# Sheet1.net
KiCad netlist of a schematic drawn in Altium Designer
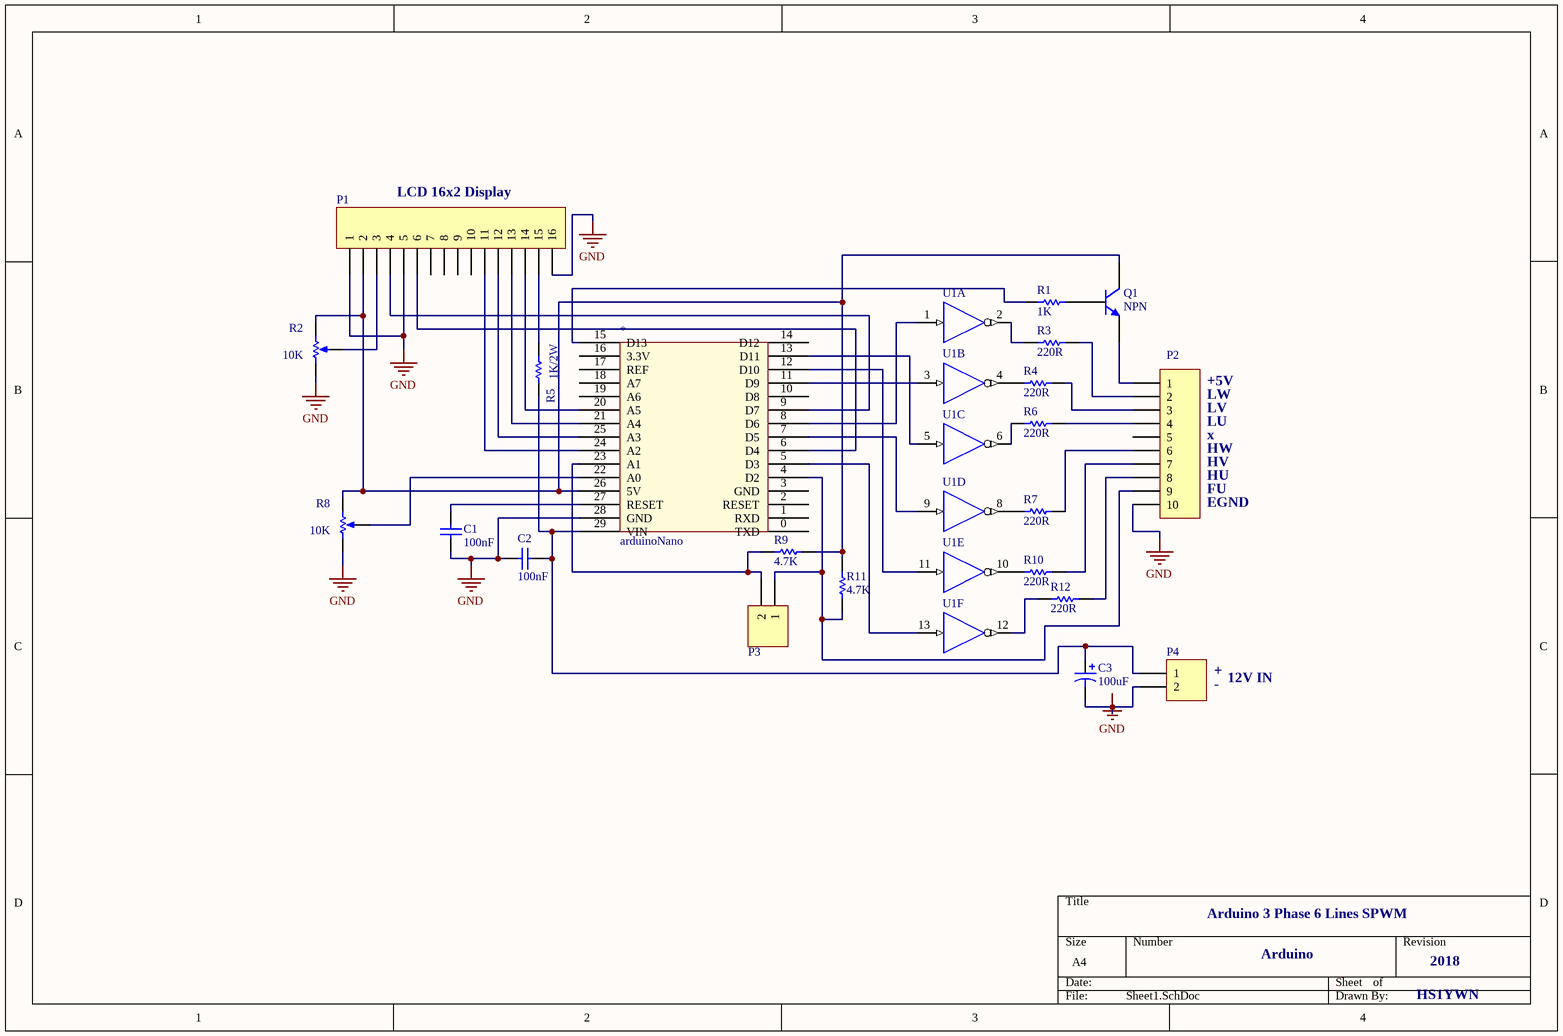
[diagram p0: Sheet1.SchDoc]

(export (version "E")
  (design (tool "Eeschema 10.0.6"))
  (components
    (comp (ref "*")
      (value "arduinoNano")
      (footprint "Arduino nano")
      (libsource (lib "nanoArduino") (part "arduinoNano"))
    )
    (comp (ref "C1")
      (value "100nF")
      (footprint "CE_200")
      (description "Capacitor")
      (fields (field (name "PUBLISHER") "Altium Limited"))
      (libsource (lib "PCB_PS21244_Project") (part "Cap"))
    )
    (comp (ref "C2")
      (value "100nF")
      (footprint "CE_200")
      (description "Capacitor")
      (fields (field (name "PUBLISHER") "Altium Limited"))
      (libsource (lib "PCB_PS21244_Project") (part "Cap"))
    )
    (comp (ref "C3")
      (value "100uF")
      (footprint "CAN_150")
      (description "Capacitor (Radial)")
      (fields (field (name "PUBLISHER") "Altium Limited"))
      (libsource (lib "PCB_PS21244_Project") (part "Cap Pol1"))
    )
    (comp (ref "P1")
      (value "Header 16")
      (footprint "HDR1X16")
      (description "Header, 16-Pin")
      (fields (field (name "PUBLISHER") "Altium Limited"))
      (libsource (lib "Miscellaneous Connectors") (part "Header 16"))
    )
    (comp (ref "P2")
      (value "Header 10")
      (footprint "HDR1X10")
      (description "Header, 10-Pin")
      (fields (field (name "PUBLISHER") "Altium Limited"))
      (libsource (lib "Miscellaneous Connectors") (part "Header 10"))
    )
    (comp (ref "P3")
      (value "Header 2")
      (footprint "HDR1X2")
      (description "Header, 2-Pin")
      (fields (field (name "PUBLISHER") "Altium Limited"))
      (libsource (lib "Miscellaneous Connectors") (part "Header 2"))
    )
    (comp (ref "P4")
      (value "Header 2")
      (footprint "HDR1X2")
      (description "Header, 2-Pin")
      (fields (field (name "PUBLISHER") "Altium Limited"))
      (libsource (lib "") (part "Header 2_1"))
    )
    (comp (ref "Q1")
      (value "NPN")
      (footprint "TO-226-AA")
      (description "NPN Bipolar Transistor")
      (fields (field (name "PUBLISHER") "Altium Limited"))
      (libsource (lib "Miscellaneous Devices") (part "NPN"))
    )
    (comp (ref "R1")
      (value "1K")
      (footprint "AXIAL-0.3")
      (description "Resistor")
      (fields (field (name "PUBLISHER") "Altium Limited"))
      (libsource (lib "Miscellaneous Devices") (part "Res1"))
    )
    (comp (ref "R2")
      (value "10K")
      (footprint "VR5")
      (description "Potentiometer")
      (fields (field (name "PUBLISHER") "Altium Limited"))
      (libsource (lib "Miscellaneous Devices") (part "RPot"))
    )
    (comp (ref "R3")
      (value "220R")
      (footprint "AXIAL-0.3")
      (description "Resistor")
      (fields (field (name "PUBLISHER") "Altium Limited"))
      (libsource (lib "Miscellaneous Devices") (part "Res1"))
    )
    (comp (ref "R4")
      (value "220R")
      (footprint "AXIAL-0.3")
      (description "Resistor")
      (fields (field (name "PUBLISHER") "Altium Limited"))
      (libsource (lib "Miscellaneous Devices") (part "Res1"))
    )
    (comp (ref "R5")
      (value "1K/2W")
      (footprint "AXIAL-0.5")
      (description "Resistor")
      (fields (field (name "PUBLISHER") "Altium Limited"))
      (libsource (lib "Miscellaneous Devices") (part "Res1"))
    )
    (comp (ref "R6")
      (value "220R")
      (footprint "AXIAL-0.3")
      (description "Resistor")
      (fields (field (name "PUBLISHER") "Altium Limited"))
      (libsource (lib "Miscellaneous Devices") (part "Res1"))
    )
    (comp (ref "R7")
      (value "220R")
      (footprint "AXIAL-0.3")
      (description "Resistor")
      (fields (field (name "PUBLISHER") "Altium Limited"))
      (libsource (lib "Miscellaneous Devices") (part "Res1"))
    )
    (comp (ref "R8")
      (value "10K")
      (footprint "VR5")
      (description "Potentiometer")
      (fields (field (name "PUBLISHER") "Altium Limited"))
      (libsource (lib "Miscellaneous Devices") (part "RPot"))
    )
    (comp (ref "R9")
      (value "4.7K")
      (footprint "AXIAL-0.3")
      (description "Resistor")
      (fields (field (name "PUBLISHER") "Altium Limited"))
      (libsource (lib "Miscellaneous Devices") (part "Res1"))
    )
    (comp (ref "R10")
      (value "220R")
      (footprint "AXIAL-0.3")
      (description "Resistor")
      (fields (field (name "PUBLISHER") "Altium Limited"))
      (libsource (lib "Miscellaneous Devices") (part "Res1"))
    )
    (comp (ref "R11")
      (value "4.7K")
      (footprint "AXIAL-0.3")
      (description "Resistor")
      (fields (field (name "PUBLISHER") "Altium Limited"))
      (libsource (lib "Miscellaneous Devices") (part "Res1"))
    )
    (comp (ref "R12")
      (value "220R")
      (footprint "AXIAL-0.3")
      (description "Resistor")
      (fields (field (name "PUBLISHER") "Altium Limited"))
      (libsource (lib "Miscellaneous Devices") (part "Res1"))
    )
    (comp (ref "U1")
      (value "M74HC04M1R")
      (footprint "SO14_N")
      (description "Hex Inverter")
      (fields (field (name "PUBLISHER") "Altium Limited"))
      (libsource (lib "PCB_PS21244_Project") (part "M74HC04M1R"))
    )
  )
  (nets
    (net (code "1") (name "GND") (class "Default")
      (node (ref "*") (pin "28") (pinfunction "GND_28") (pintype "passive"))
      (node (ref "C1") (pin "1") (pinfunction "1_1") (pintype "passive"))
      (node (ref "C2") (pin "2") (pinfunction "2_2") (pintype "passive"))
      (node (ref "P1") (pin "1") (pinfunction "1_1") (pintype "passive"))
      (node (ref "P1") (pin "16") (pinfunction "16_16") (pintype "passive"))
      (node (ref "P1") (pin "5") (pinfunction "5_5") (pintype "passive"))
      (node (ref "P2") (pin "10") (pinfunction "10_10") (pintype "passive"))
      (node (ref "R2") (pin "1") (pinfunction "TOP_1") (pintype "passive"))
      (node (ref "R8") (pin "1") (pinfunction "TOP_1") (pintype "passive"))
      (node (ref "U1") (pin "7") (pinfunction "GND_7") (pintype "power_in"))
    )
    (net (code "2") (name "Net-(*-5V)") (class "Default")
      (node (ref "*") (pin "26") (pinfunction "5V_26") (pintype "passive"))
      (node (ref "P1") (pin "2") (pinfunction "2_2") (pintype "passive"))
      (node (ref "Q1") (pin "1") (pinfunction "C_1") (pintype "passive"))
      (node (ref "R11") (pin "1") (pinfunction "1_1") (pintype "passive"))
      (node (ref "R2") (pin "2") (pinfunction "BOT_2") (pintype "passive"))
      (node (ref "R8") (pin "2") (pinfunction "BOT_2") (pintype "passive"))
      (node (ref "R9") (pin "2") (pinfunction "2_2") (pintype "passive"))
    )
    (net (code "3") (name "Net-(*-A0)") (class "Default")
      (node (ref "*") (pin "22") (pinfunction "A0_22") (pintype "passive"))
      (node (ref "R8") (pin "3") (pinfunction "TAP_3") (pintype "passive"))
    )
    (net (code "4") (name "Net-(*-A1)") (class "Default")
      (node (ref "*") (pin "23") (pinfunction "A1_23") (pintype "passive"))
      (node (ref "P3") (pin "2") (pinfunction "2_2") (pintype "passive"))
      (node (ref "R9") (pin "1") (pinfunction "1_1") (pintype "passive"))
    )
    (net (code "5") (name "Net-(*-A2)") (class "Default")
      (node (ref "*") (pin "24") (pinfunction "A2_24") (pintype "passive"))
      (node (ref "P1") (pin "11") (pinfunction "11_11") (pintype "passive"))
    )
    (net (code "6") (name "Net-(*-A3)") (class "Default")
      (node (ref "*") (pin "25") (pinfunction "A3_25") (pintype "passive"))
      (node (ref "P1") (pin "12") (pinfunction "12_12") (pintype "passive"))
    )
    (net (code "7") (name "Net-(*-A4)") (class "Default")
      (node (ref "*") (pin "21") (pinfunction "A4_21") (pintype "passive"))
      (node (ref "P1") (pin "13") (pinfunction "13_13") (pintype "passive"))
    )
    (net (code "8") (name "Net-(*-A5)") (class "Default")
      (node (ref "*") (pin "20") (pinfunction "A5_20") (pintype "passive"))
      (node (ref "P1") (pin "14") (pinfunction "14_14") (pintype "passive"))
    )
    (net (code "9") (name "Net-(*-D2)") (class "Default")
      (node (ref "*") (pin "4") (pinfunction "D2_4") (pintype "passive"))
      (node (ref "P2") (pin "9") (pinfunction "9_9") (pintype "passive"))
      (node (ref "P3") (pin "1") (pinfunction "1_1") (pintype "passive"))
      (node (ref "R11") (pin "2") (pinfunction "2_2") (pintype "passive"))
    )
    (net (code "10") (name "Net-(*-D3)") (class "Default")
      (node (ref "*") (pin "5") (pinfunction "D3_5") (pintype "passive"))
      (node (ref "U1") (pin "13") (pinfunction "A_13") (pintype "input"))
    )
    (net (code "11") (name "Net-(*-D4)") (class "Default")
      (node (ref "*") (pin "6") (pinfunction "D4_6") (pintype "passive"))
      (node (ref "P1") (pin "6") (pinfunction "6_6") (pintype "passive"))
    )
    (net (code "12") (name "Net-(*-D5)") (class "Default")
      (node (ref "*") (pin "7") (pinfunction "D5_7") (pintype "passive"))
      (node (ref "U1") (pin "9") (pinfunction "A_9") (pintype "input"))
    )
    (net (code "13") (name "Net-(*-D6)") (class "Default")
      (node (ref "*") (pin "8") (pinfunction "D6_8") (pintype "passive"))
      (node (ref "U1") (pin "1") (pinfunction "A_1") (pintype "input"))
    )
    (net (code "14") (name "Net-(*-D7)") (class "Default")
      (node (ref "*") (pin "9") (pinfunction "D7_9") (pintype "passive"))
      (node (ref "P1") (pin "4") (pinfunction "4_4") (pintype "passive"))
    )
    (net (code "15") (name "Net-(*-D9)") (class "Default")
      (node (ref "*") (pin "11") (pinfunction "D9_11") (pintype "passive"))
      (node (ref "U1") (pin "3") (pinfunction "A_3") (pintype "input"))
    )
    (net (code "16") (name "Net-(*-D10)") (class "Default")
      (node (ref "*") (pin "12") (pinfunction "D10_12") (pintype "passive"))
      (node (ref "U1") (pin "11") (pinfunction "A_11") (pintype "input"))
    )
    (net (code "17") (name "Net-(*-D11)") (class "Default")
      (node (ref "*") (pin "13") (pinfunction "D11_13") (pintype "passive"))
      (node (ref "U1") (pin "5") (pinfunction "A_5") (pintype "input"))
    )
    (net (code "18") (name "Net-(*-D13)") (class "Default")
      (node (ref "*") (pin "15") (pinfunction "D13_15") (pintype "passive"))
      (node (ref "R1") (pin "2") (pinfunction "2_2") (pintype "passive"))
    )
    (net (code "19") (name "Net-(*-RESET-Pad27)") (class "Default")
      (node (ref "*") (pin "27") (pinfunction "RESET_27") (pintype "passive"))
      (node (ref "C1") (pin "2") (pinfunction "2_2") (pintype "passive"))
    )
    (net (code "20") (name "Net-(*-VIN)") (class "Default")
      (node (ref "*") (pin "29") (pinfunction "VIN_29") (pintype "passive"))
      (node (ref "C2") (pin "1") (pinfunction "1_1") (pintype "passive"))
      (node (ref "C3") (pin "1") (pinfunction "1_1") (pintype "passive"))
      (node (ref "P4") (pin "1") (pinfunction "1_1") (pintype "passive"))
      (node (ref "R5") (pin "1") (pinfunction "1_1") (pintype "passive"))
    )
    (net (code "21") (name "Net-(C3-Pad2)") (class "Default")
      (node (ref "C3") (pin "2") (pinfunction "2_2") (pintype "passive"))
      (node (ref "P4") (pin "2") (pinfunction "2_2") (pintype "passive"))
    )
    (net (code "22") (name "Net-(P1-Pad15)") (class "Default")
      (node (ref "P1") (pin "15") (pinfunction "15_15") (pintype "passive"))
      (node (ref "R5") (pin "2") (pinfunction "2_2") (pintype "passive"))
    )
    (net (code "23") (name "Net-(P2-Pad2)") (class "Default")
      (node (ref "P2") (pin "2") (pinfunction "2_2") (pintype "passive"))
      (node (ref "R3") (pin "1") (pinfunction "1_1") (pintype "passive"))
    )
    (net (code "24") (name "Net-(P2-Pad3)") (class "Default")
      (node (ref "P2") (pin "3") (pinfunction "3_3") (pintype "passive"))
      (node (ref "R4") (pin "1") (pinfunction "1_1") (pintype "passive"))
    )
    (net (code "25") (name "Net-(P2-Pad4)") (class "Default")
      (node (ref "P2") (pin "4") (pinfunction "4_4") (pintype "passive"))
      (node (ref "R6") (pin "1") (pinfunction "1_1") (pintype "passive"))
    )
    (net (code "26") (name "Net-(P2-Pad6)") (class "Default")
      (node (ref "P2") (pin "6") (pinfunction "6_6") (pintype "passive"))
      (node (ref "R7") (pin "1") (pinfunction "1_1") (pintype "passive"))
    )
    (net (code "27") (name "Net-(P2-Pad7)") (class "Default")
      (node (ref "P2") (pin "7") (pinfunction "7_7") (pintype "passive"))
      (node (ref "R10") (pin "1") (pinfunction "1_1") (pintype "passive"))
    )
    (net (code "28") (name "Net-(P2-Pad8)") (class "Default")
      (node (ref "P2") (pin "8") (pinfunction "8_8") (pintype "passive"))
      (node (ref "R12") (pin "1") (pinfunction "1_1") (pintype "passive"))
    )
    (net (code "29") (name "Net-(Q1-B)") (class "Default")
      (node (ref "Q1") (pin "2") (pinfunction "B_2") (pintype "passive"))
      (node (ref "R1") (pin "1") (pinfunction "1_1") (pintype "passive"))
    )
    (net (code "30") (name "Net-(Q1-E)") (class "Default")
      (node (ref "P2") (pin "1") (pinfunction "1_1") (pintype "passive"))
      (node (ref "Q1") (pin "3") (pinfunction "E_3") (pintype "passive"))
    )
    (net (code "31") (name "Net-(R2-TAP)") (class "Default")
      (node (ref "P1") (pin "3") (pinfunction "3_3") (pintype "passive"))
      (node (ref "R2") (pin "3") (pinfunction "TAP_3") (pintype "passive"))
    )
    (net (code "32") (name "Net-(U1A-Y)") (class "Default")
      (node (ref "R3") (pin "2") (pinfunction "2_2") (pintype "passive"))
      (node (ref "U1") (pin "2") (pinfunction "Y_2") (pintype "output"))
    )
    (net (code "33") (name "Net-(U1B-Y)") (class "Default")
      (node (ref "R4") (pin "2") (pinfunction "2_2") (pintype "passive"))
      (node (ref "U1") (pin "4") (pinfunction "Y_4") (pintype "output"))
    )
    (net (code "34") (name "Net-(U1C-Y)") (class "Default")
      (node (ref "R6") (pin "2") (pinfunction "2_2") (pintype "passive"))
      (node (ref "U1") (pin "6") (pinfunction "Y_6") (pintype "output"))
    )
    (net (code "35") (name "Net-(U1D-Y)") (class "Default")
      (node (ref "R7") (pin "2") (pinfunction "2_2") (pintype "passive"))
      (node (ref "U1") (pin "8") (pinfunction "Y_8") (pintype "output"))
    )
    (net (code "36") (name "Net-(U1E-Y)") (class "Default")
      (node (ref "R10") (pin "2") (pinfunction "2_2") (pintype "passive"))
      (node (ref "U1") (pin "10") (pinfunction "Y_10") (pintype "output"))
    )
    (net (code "37") (name "Net-(U1F-Y)") (class "Default")
      (node (ref "R12") (pin "2") (pinfunction "2_2") (pintype "passive"))
      (node (ref "U1") (pin "12") (pinfunction "Y_12") (pintype "output"))
    )
    (net (code "38") (name "VCC") (class "Default")
      (node (ref "U1") (pin "14") (pinfunction "VCC_14") (pintype "power_in"))
    )
    (net (code "39") (name "unconnected-(*-3.3V-Pad16)") (class "Default")
      (node (ref "*") (pin "16") (pinfunction "3.3V_16") (pintype "passive"))
    )
    (net (code "40") (name "unconnected-(*-A6-Pad19)") (class "Default")
      (node (ref "*") (pin "19") (pinfunction "A6_19") (pintype "passive"))
    )
    (net (code "41") (name "unconnected-(*-A7-Pad18)") (class "Default")
      (node (ref "*") (pin "18") (pinfunction "A7_18") (pintype "passive"))
    )
    (net (code "42") (name "unconnected-(*-D8-Pad10)") (class "Default")
      (node (ref "*") (pin "10") (pinfunction "D8_10") (pintype "passive"))
    )
    (net (code "43") (name "unconnected-(*-D12-Pad14)") (class "Default")
      (node (ref "*") (pin "14") (pinfunction "D12_14") (pintype "passive"))
    )
    (net (code "44") (name "unconnected-(*-GND-Pad3)") (class "Default")
      (node (ref "*") (pin "3") (pinfunction "GND_3") (pintype "passive"))
    )
    (net (code "45") (name "unconnected-(*-REF-Pad17)") (class "Default")
      (node (ref "*") (pin "17") (pinfunction "REF_17") (pintype "passive"))
    )
    (net (code "46") (name "unconnected-(*-RESET-Pad2)") (class "Default")
      (node (ref "*") (pin "2") (pinfunction "RESET_2") (pintype "passive"))
    )
    (net (code "47") (name "unconnected-(*-RXD-Pad1)") (class "Default")
      (node (ref "*") (pin "1") (pinfunction "RXD_1") (pintype "passive"))
    )
    (net (code "48") (name "unconnected-(*-TXD-Pad0)") (class "Default")
      (node (ref "*") (pin "0") (pinfunction "TXD_0") (pintype "passive"))
    )
    (net (code "49") (name "unconnected-(P1-Pad7)") (class "Default")
      (node (ref "P1") (pin "7") (pinfunction "7_7") (pintype "passive"))
    )
    (net (code "50") (name "unconnected-(P1-Pad8)") (class "Default")
      (node (ref "P1") (pin "8") (pinfunction "8_8") (pintype "passive"))
    )
    (net (code "51") (name "unconnected-(P1-Pad9)") (class "Default")
      (node (ref "P1") (pin "9") (pinfunction "9_9") (pintype "passive"))
    )
    (net (code "52") (name "unconnected-(P1-Pad10)") (class "Default")
      (node (ref "P1") (pin "10") (pinfunction "10_10") (pintype "passive"))
    )
    (net (code "53") (name "unconnected-(P2-Pad5)") (class "Default")
      (node (ref "P2") (pin "5") (pinfunction "5_5") (pintype "passive"))
    )
  )
)
